# W020B.net
KiCad netlist of a schematic drawn in EAGLE
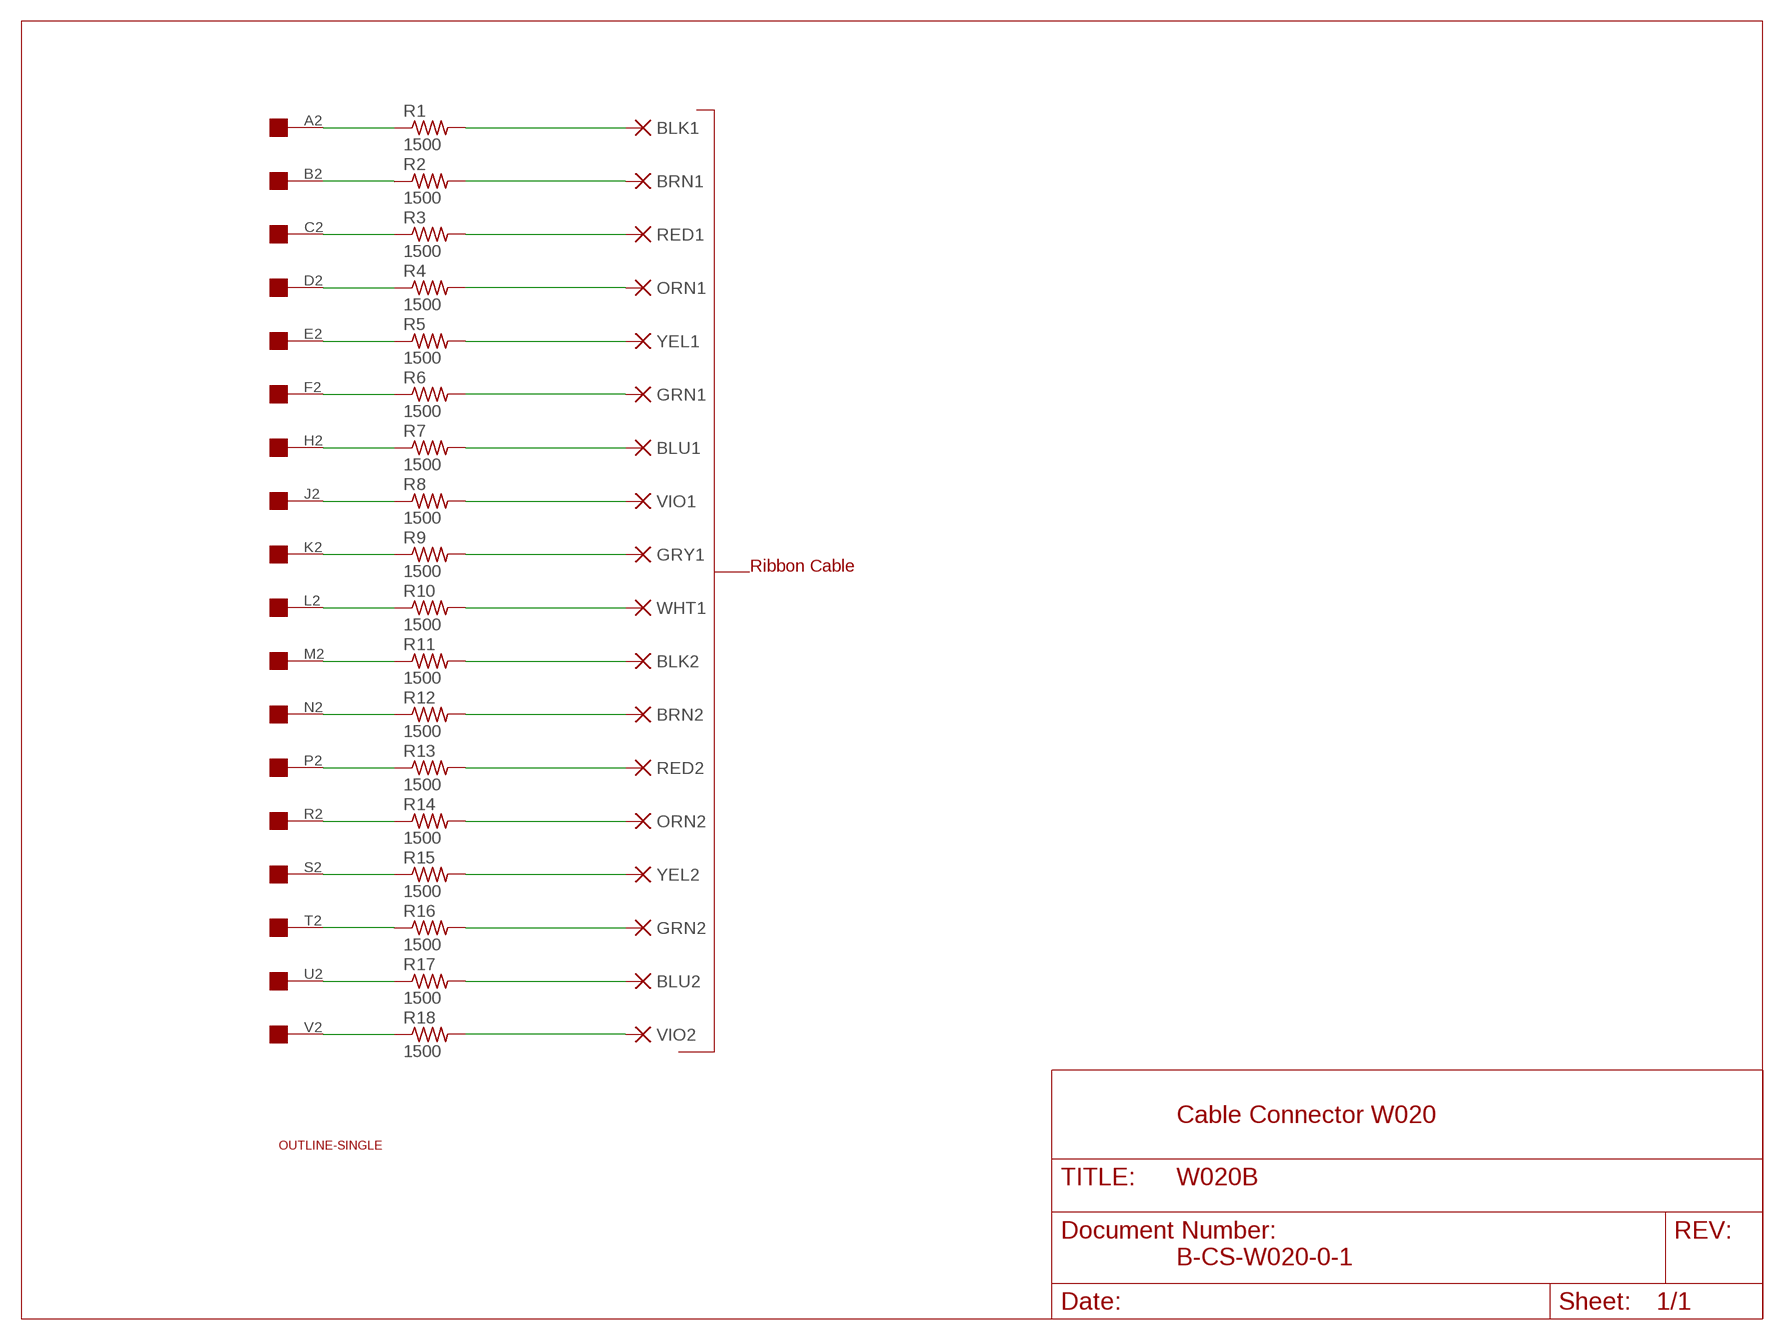
[diagram p0: schematic, sheet 1]

(export (version "E")
  (design (tool "Eeschema 10.0.6"))
  (components
    (comp (ref "BLK1")
      (value "PAD-0465")
      (footprint "eagle-import:0465")
      (libsource (lib "eagle-import") (part "PAD-0465"))
    )
    (comp (ref "BLK2")
      (value "PAD-0465")
      (footprint "eagle-import:0465")
      (libsource (lib "eagle-import") (part "PAD-0465"))
    )
    (comp (ref "BLU1")
      (value "PAD-0465")
      (footprint "eagle-import:0465")
      (libsource (lib "eagle-import") (part "PAD-0465"))
    )
    (comp (ref "BLU2")
      (value "PAD-0465")
      (footprint "eagle-import:0465")
      (libsource (lib "eagle-import") (part "PAD-0465"))
    )
    (comp (ref "BRN1")
      (value "PAD-0465")
      (footprint "eagle-import:0465")
      (libsource (lib "eagle-import") (part "PAD-0465"))
    )
    (comp (ref "BRN2")
      (value "PAD-0465")
      (footprint "eagle-import:0465")
      (libsource (lib "eagle-import") (part "PAD-0465"))
    )
    (comp (ref "GRN1")
      (value "PAD-0465")
      (footprint "eagle-import:0465")
      (libsource (lib "eagle-import") (part "PAD-0465"))
    )
    (comp (ref "GRN2")
      (value "PAD-0465")
      (footprint "eagle-import:0465")
      (libsource (lib "eagle-import") (part "PAD-0465"))
    )
    (comp (ref "GRY1")
      (value "PAD-0465")
      (footprint "eagle-import:0465")
      (libsource (lib "eagle-import") (part "PAD-0465"))
    )
    (comp (ref "ORN1")
      (value "PAD-0465")
      (footprint "eagle-import:0465")
      (libsource (lib "eagle-import") (part "PAD-0465"))
    )
    (comp (ref "ORN2")
      (value "PAD-0465")
      (footprint "eagle-import:0465")
      (libsource (lib "eagle-import") (part "PAD-0465"))
    )
    (comp (ref "R1")
      (value "1500")
      (footprint "eagle-import:0207_10")
      (libsource (lib "eagle-import") (part "R-US_0207/10"))
    )
    (comp (ref "R2")
      (value "1500")
      (footprint "eagle-import:0207_10")
      (libsource (lib "eagle-import") (part "R-US_0207/10"))
    )
    (comp (ref "R3")
      (value "1500")
      (footprint "eagle-import:0207_10")
      (libsource (lib "eagle-import") (part "R-US_0207/10"))
    )
    (comp (ref "R4")
      (value "1500")
      (footprint "eagle-import:0207_10")
      (libsource (lib "eagle-import") (part "R-US_0207/10"))
    )
    (comp (ref "R5")
      (value "1500")
      (footprint "eagle-import:0207_10")
      (libsource (lib "eagle-import") (part "R-US_0207/10"))
    )
    (comp (ref "R6")
      (value "1500")
      (footprint "eagle-import:0207_10")
      (libsource (lib "eagle-import") (part "R-US_0207/10"))
    )
    (comp (ref "R7")
      (value "1500")
      (footprint "eagle-import:0207_10")
      (libsource (lib "eagle-import") (part "R-US_0207/10"))
    )
    (comp (ref "R8")
      (value "1500")
      (footprint "eagle-import:0207_10")
      (libsource (lib "eagle-import") (part "R-US_0207/10"))
    )
    (comp (ref "R9")
      (value "1500")
      (footprint "eagle-import:0207_10")
      (libsource (lib "eagle-import") (part "R-US_0207/10"))
    )
    (comp (ref "R10")
      (value "1500")
      (footprint "eagle-import:0207_10")
      (libsource (lib "eagle-import") (part "R-US_0207/10"))
    )
    (comp (ref "R11")
      (value "1500")
      (footprint "eagle-import:0207_10")
      (libsource (lib "eagle-import") (part "R-US_0207/10"))
    )
    (comp (ref "R12")
      (value "1500")
      (footprint "eagle-import:0207_10")
      (libsource (lib "eagle-import") (part "R-US_0207/10"))
    )
    (comp (ref "R13")
      (value "1500")
      (footprint "eagle-import:0207_10")
      (libsource (lib "eagle-import") (part "R-US_0207/10"))
    )
    (comp (ref "R14")
      (value "1500")
      (footprint "eagle-import:0207_10")
      (libsource (lib "eagle-import") (part "R-US_0207/10"))
    )
    (comp (ref "R15")
      (value "1500")
      (footprint "eagle-import:0207_10")
      (libsource (lib "eagle-import") (part "R-US_0207/10"))
    )
    (comp (ref "R16")
      (value "1500")
      (footprint "eagle-import:0207_10")
      (libsource (lib "eagle-import") (part "R-US_0207/10"))
    )
    (comp (ref "R17")
      (value "1500")
      (footprint "eagle-import:0207_10")
      (libsource (lib "eagle-import") (part "R-US_0207/10"))
    )
    (comp (ref "R18")
      (value "1500")
      (footprint "eagle-import:0207_10")
      (libsource (lib "eagle-import") (part "R-US_0207/10"))
    )
    (comp (ref "RED1")
      (value "PAD-0465")
      (footprint "eagle-import:0465")
      (libsource (lib "eagle-import") (part "PAD-0465"))
    )
    (comp (ref "RED2")
      (value "PAD-0465")
      (footprint "eagle-import:0465")
      (libsource (lib "eagle-import") (part "PAD-0465"))
    )
    (comp (ref "U$1")
      (value "OUTLINE-SINGLE")
      (footprint "eagle-import:SINGLE")
      (libsource (lib "eagle-import") (part "OUTLINE-SINGLE"))
    )
    (comp (ref "U$2")
      (value "EDGE-1")
      (footprint "eagle-import:EDGE-CON1")
      (libsource (lib "eagle-import") (part "EDGE-1"))
    )
    (comp (ref "VIO1")
      (value "PAD-0465")
      (footprint "eagle-import:0465")
      (libsource (lib "eagle-import") (part "PAD-0465"))
    )
    (comp (ref "VIO2")
      (value "PAD-0465")
      (footprint "eagle-import:0465")
      (libsource (lib "eagle-import") (part "PAD-0465"))
    )
    (comp (ref "WHT1")
      (value "PAD-0465")
      (footprint "eagle-import:0465")
      (libsource (lib "eagle-import") (part "PAD-0465"))
    )
    (comp (ref "YEL1")
      (value "PAD-0465")
      (footprint "eagle-import:0465")
      (libsource (lib "eagle-import") (part "PAD-0465"))
    )
    (comp (ref "YEL2")
      (value "PAD-0465")
      (footprint "eagle-import:0465")
      (libsource (lib "eagle-import") (part "PAD-0465"))
    )
  )
  (nets
    (net (code "1") (name "Net-(BLK1-P)") (class "Default")
      (node (ref "BLK1") (pin "P$1") (pinfunction "P_P$1") (pintype "passive"))
      (node (ref "R1") (pin "2") (pinfunction "2_2") (pintype "passive"))
    )
    (net (code "2") (name "Net-(BLK2-P)") (class "Default")
      (node (ref "BLK2") (pin "P$1") (pinfunction "P_P$1") (pintype "passive"))
      (node (ref "R11") (pin "2") (pinfunction "2_2") (pintype "passive"))
    )
    (net (code "3") (name "Net-(BLU1-P)") (class "Default")
      (node (ref "BLU1") (pin "P$1") (pinfunction "P_P$1") (pintype "passive"))
      (node (ref "R7") (pin "2") (pinfunction "2_2") (pintype "passive"))
    )
    (net (code "4") (name "Net-(BLU2-P)") (class "Default")
      (node (ref "BLU2") (pin "P$1") (pinfunction "P_P$1") (pintype "passive"))
      (node (ref "R17") (pin "2") (pinfunction "2_2") (pintype "passive"))
    )
    (net (code "5") (name "Net-(BRN1-P)") (class "Default")
      (node (ref "BRN1") (pin "P$1") (pinfunction "P_P$1") (pintype "passive"))
      (node (ref "R2") (pin "2") (pinfunction "2_2") (pintype "passive"))
    )
    (net (code "6") (name "Net-(BRN2-P)") (class "Default")
      (node (ref "BRN2") (pin "P$1") (pinfunction "P_P$1") (pintype "passive"))
      (node (ref "R12") (pin "2") (pinfunction "2_2") (pintype "passive"))
    )
    (net (code "7") (name "Net-(GRN1-P)") (class "Default")
      (node (ref "GRN1") (pin "P$1") (pinfunction "P_P$1") (pintype "passive"))
      (node (ref "R6") (pin "2") (pinfunction "2_2") (pintype "passive"))
    )
    (net (code "8") (name "Net-(GRN2-P)") (class "Default")
      (node (ref "GRN2") (pin "P$1") (pinfunction "P_P$1") (pintype "passive"))
      (node (ref "R16") (pin "2") (pinfunction "2_2") (pintype "passive"))
    )
    (net (code "9") (name "Net-(GRY1-P)") (class "Default")
      (node (ref "GRY1") (pin "P$1") (pinfunction "P_P$1") (pintype "passive"))
      (node (ref "R9") (pin "2") (pinfunction "2_2") (pintype "passive"))
    )
    (net (code "10") (name "Net-(ORN1-P)") (class "Default")
      (node (ref "ORN1") (pin "P$1") (pinfunction "P_P$1") (pintype "passive"))
      (node (ref "R4") (pin "2") (pinfunction "2_2") (pintype "passive"))
    )
    (net (code "11") (name "Net-(ORN2-P)") (class "Default")
      (node (ref "ORN2") (pin "P$1") (pinfunction "P_P$1") (pintype "passive"))
      (node (ref "R14") (pin "2") (pinfunction "2_2") (pintype "passive"))
    )
    (net (code "12") (name "Net-(RED1-P)") (class "Default")
      (node (ref "R3") (pin "2") (pinfunction "2_2") (pintype "passive"))
      (node (ref "RED1") (pin "P$1") (pinfunction "P_P$1") (pintype "passive"))
    )
    (net (code "13") (name "Net-(RED2-P)") (class "Default")
      (node (ref "R13") (pin "2") (pinfunction "2_2") (pintype "passive"))
      (node (ref "RED2") (pin "P$1") (pinfunction "P_P$1") (pintype "passive"))
    )
    (net (code "14") (name "Net-(U$2A-1)") (class "Default")
      (node (ref "R1") (pin "1") (pinfunction "1_1") (pintype "passive"))
      (node (ref "U$2") (pin "A2") (pinfunction "1_A2") (pintype "bidirectional"))
    )
    (net (code "15") (name "Net-(U$2B-1)") (class "Default")
      (node (ref "R2") (pin "1") (pinfunction "1_1") (pintype "passive"))
      (node (ref "U$2") (pin "B2") (pinfunction "1_B2") (pintype "bidirectional"))
    )
    (net (code "16") (name "Net-(U$2C-1)") (class "Default")
      (node (ref "R3") (pin "1") (pinfunction "1_1") (pintype "passive"))
      (node (ref "U$2") (pin "C2") (pinfunction "1_C2") (pintype "bidirectional"))
    )
    (net (code "17") (name "Net-(U$2D-1)") (class "Default")
      (node (ref "R4") (pin "1") (pinfunction "1_1") (pintype "passive"))
      (node (ref "U$2") (pin "D2") (pinfunction "1_D2") (pintype "bidirectional"))
    )
    (net (code "18") (name "Net-(U$2E-1)") (class "Default")
      (node (ref "R5") (pin "1") (pinfunction "1_1") (pintype "passive"))
      (node (ref "U$2") (pin "E2") (pinfunction "1_E2") (pintype "bidirectional"))
    )
    (net (code "19") (name "Net-(U$2F-1)") (class "Default")
      (node (ref "R6") (pin "1") (pinfunction "1_1") (pintype "passive"))
      (node (ref "U$2") (pin "F2") (pinfunction "1_F2") (pintype "bidirectional"))
    )
    (net (code "20") (name "Net-(U$2G-1)") (class "Default")
      (node (ref "R7") (pin "1") (pinfunction "1_1") (pintype "passive"))
      (node (ref "U$2") (pin "H2") (pinfunction "1_H2") (pintype "bidirectional"))
    )
    (net (code "21") (name "Net-(U$2H-1)") (class "Default")
      (node (ref "R8") (pin "1") (pinfunction "1_1") (pintype "passive"))
      (node (ref "U$2") (pin "J2") (pinfunction "1_J2") (pintype "bidirectional"))
    )
    (net (code "22") (name "Net-(U$2I-1)") (class "Default")
      (node (ref "R9") (pin "1") (pinfunction "1_1") (pintype "passive"))
      (node (ref "U$2") (pin "K2") (pinfunction "1_K2") (pintype "bidirectional"))
    )
    (net (code "23") (name "Net-(U$2J-1)") (class "Default")
      (node (ref "R10") (pin "1") (pinfunction "1_1") (pintype "passive"))
      (node (ref "U$2") (pin "L2") (pinfunction "1_L2") (pintype "bidirectional"))
    )
    (net (code "24") (name "Net-(U$2K-1)") (class "Default")
      (node (ref "R11") (pin "1") (pinfunction "1_1") (pintype "passive"))
      (node (ref "U$2") (pin "M2") (pinfunction "1_M2") (pintype "bidirectional"))
    )
    (net (code "25") (name "Net-(U$2L-1)") (class "Default")
      (node (ref "R12") (pin "1") (pinfunction "1_1") (pintype "passive"))
      (node (ref "U$2") (pin "N2") (pinfunction "1_N2") (pintype "bidirectional"))
    )
    (net (code "26") (name "Net-(U$2M-1)") (class "Default")
      (node (ref "R13") (pin "1") (pinfunction "1_1") (pintype "passive"))
      (node (ref "U$2") (pin "P2") (pinfunction "1_P2") (pintype "bidirectional"))
    )
    (net (code "27") (name "Net-(U$2N-1)") (class "Default")
      (node (ref "R14") (pin "1") (pinfunction "1_1") (pintype "passive"))
      (node (ref "U$2") (pin "R2") (pinfunction "1_R2") (pintype "bidirectional"))
    )
    (net (code "28") (name "Net-(U$2O-1)") (class "Default")
      (node (ref "R15") (pin "1") (pinfunction "1_1") (pintype "passive"))
      (node (ref "U$2") (pin "S2") (pinfunction "1_S2") (pintype "bidirectional"))
    )
    (net (code "29") (name "Net-(U$2P-1)") (class "Default")
      (node (ref "R16") (pin "1") (pinfunction "1_1") (pintype "passive"))
      (node (ref "U$2") (pin "T2") (pinfunction "1_T2") (pintype "bidirectional"))
    )
    (net (code "30") (name "Net-(U$2Q-1)") (class "Default")
      (node (ref "R17") (pin "1") (pinfunction "1_1") (pintype "passive"))
      (node (ref "U$2") (pin "U2") (pinfunction "1_U2") (pintype "bidirectional"))
    )
    (net (code "31") (name "Net-(U$2R-1)") (class "Default")
      (node (ref "R18") (pin "1") (pinfunction "1_1") (pintype "passive"))
      (node (ref "U$2") (pin "V2") (pinfunction "1_V2") (pintype "bidirectional"))
    )
    (net (code "32") (name "Net-(VIO1-P)") (class "Default")
      (node (ref "R8") (pin "2") (pinfunction "2_2") (pintype "passive"))
      (node (ref "VIO1") (pin "P$1") (pinfunction "P_P$1") (pintype "passive"))
    )
    (net (code "33") (name "Net-(VIO2-P)") (class "Default")
      (node (ref "R18") (pin "2") (pinfunction "2_2") (pintype "passive"))
      (node (ref "VIO2") (pin "P$1") (pinfunction "P_P$1") (pintype "passive"))
    )
    (net (code "34") (name "Net-(WHT1-P)") (class "Default")
      (node (ref "R10") (pin "2") (pinfunction "2_2") (pintype "passive"))
      (node (ref "WHT1") (pin "P$1") (pinfunction "P_P$1") (pintype "passive"))
    )
    (net (code "35") (name "Net-(YEL1-P)") (class "Default")
      (node (ref "R5") (pin "2") (pinfunction "2_2") (pintype "passive"))
      (node (ref "YEL1") (pin "P$1") (pinfunction "P_P$1") (pintype "passive"))
    )
    (net (code "36") (name "Net-(YEL2-P)") (class "Default")
      (node (ref "R15") (pin "2") (pinfunction "2_2") (pintype "passive"))
      (node (ref "YEL2") (pin "P$1") (pinfunction "P_P$1") (pintype "passive"))
    )
  )
)
